# mach_nguyen_ly.net
KiCad netlist of a schematic drawn in Altium Designer
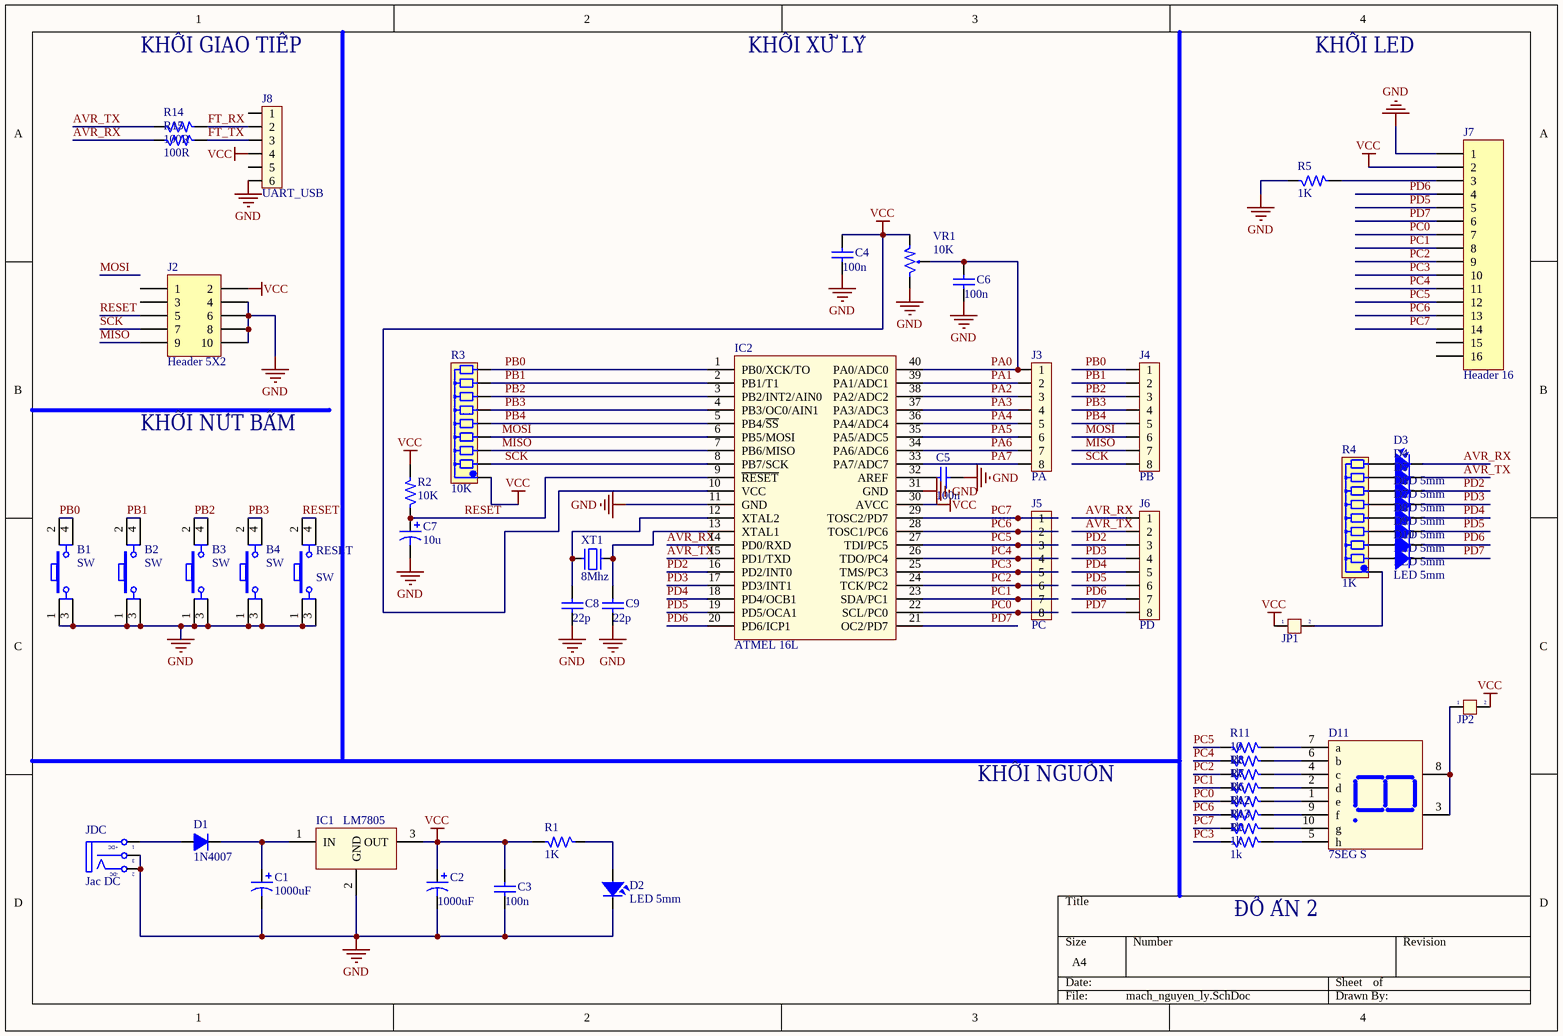
[diagram p0: mach_nguyen_ly.SchDoc]

(export (version "E")
  (design (tool "Eeschema 10.0.6"))
  (components
    (comp (ref "10")
      (value "1k")
      (footprint "R1/6W")
      (description "Resistor 1/4W")
      (libsource (lib "Cty1") (part "Res"))
    )
    (comp (ref "B1")
      (value "SW")
      (footprint "SW4")
      (description "Switch button 4 pin")
      (libsource (lib "Cty1") (part "SW4"))
    )
    (comp (ref "B2")
      (value "SW")
      (footprint "SW4")
      (description "Switch button 4 pin")
      (libsource (lib "Cty1") (part "SW4"))
    )
    (comp (ref "B3")
      (value "SW")
      (footprint "SW4")
      (description "Switch button 4 pin")
      (libsource (lib "Cty1") (part "SW4"))
    )
    (comp (ref "B4")
      (value "SW")
      (footprint "SW4")
      (description "Switch button 4 pin")
      (libsource (lib "Cty1") (part "SW4"))
    )
    (comp (ref "C1")
      (value "1000uF")
      (footprint "C10mm")
      (description "Polarized Capacitor (Axial)")
      (fields (field (name "PUBLISHER") "Altium Limited"))
      (libsource (lib "Cty1") (part "Cap Pol 12mm"))
    )
    (comp (ref "C2")
      (value "1000uF")
      (footprint "C10mm")
      (description "Polarized Capacitor (Axial)")
      (fields (field (name "PUBLISHER") "Altium Limited"))
      (libsource (lib "Cty1") (part "Cap Pol 12mm"))
    )
    (comp (ref "C3")
      (value "100n")
      (footprint "Tu-ceramic")
      (description "Capacitor")
      (fields (field (name "Comment") "Capacitor Ceramic") (field (name "PUBLISHER") "Altium Limited"))
      (libsource (lib "Cty1") (part "CapDecop"))
    )
    (comp (ref "C4")
      (value "100n")
      (footprint "Tu-ceramic")
      (description "Capacitor")
      (fields (field (name "Comment") "Capacitor Ceramic") (field (name "PUBLISHER") "Altium Limited"))
      (libsource (lib "Cty1") (part "CapDecop"))
    )
    (comp (ref "C5")
      (value "100n")
      (footprint "Tu-ceramic")
      (description "Capacitor")
      (fields (field (name "Comment") "Capacitor Ceramic") (field (name "PUBLISHER") "Altium Limited"))
      (libsource (lib "Cty1") (part "CapDecop"))
    )
    (comp (ref "C6")
      (value "100n")
      (footprint "Tu-ceramic")
      (description "Capacitor")
      (fields (field (name "Comment") "Capacitor Ceramic") (field (name "PUBLISHER") "Altium Limited"))
      (libsource (lib "Cty1") (part "CapDecop"))
    )
    (comp (ref "C7")
      (value "10u")
      (footprint "C5mm")
      (description "Polarized Capacitor (Axial)")
      (fields (field (name "PUBLISHER") "Altium Limited"))
      (libsource (lib "Cty1") (part "Cap Pol 5mm"))
    )
    (comp (ref "C8")
      (value "22p")
      (footprint "Tu-ceramic")
      (description "Capacitor")
      (fields (field (name "Comment") "Capacitor Ceramic") (field (name "PUBLISHER") "Altium Limited"))
      (libsource (lib "Cty1") (part "CapDecop"))
    )
    (comp (ref "C9")
      (value "22p")
      (footprint "Tu-ceramic")
      (description "Capacitor")
      (fields (field (name "Comment") "Capacitor Ceramic") (field (name "PUBLISHER") "Altium Limited"))
      (libsource (lib "Cty1") (part "CapDecop"))
    )
    (comp (ref "D1")
      (value "1N4007")
      (footprint "D1A")
      (description "Diode 1A")
      (libsource (lib "Cty1") (part "D1A"))
    )
    (comp (ref "D2")
      (value "LED 5mm")
      (footprint "LED-3")
      (description "LED Single colour Green and Red")
      (libsource (lib "VioletofSun") (part "LED"))
    )
    (comp (ref "D3")
      (value "LED 5mm")
      (footprint "LED-3")
      (description "LED Single colour Green and Red")
      (libsource (lib "VioletofSun") (part "LED"))
    )
    (comp (ref "D4")
      (value "LED 5mm")
      (footprint "LED-3")
      (description "LED Single colour Green and Red")
      (libsource (lib "VioletofSun") (part "LED"))
    )
    (comp (ref "D5")
      (value "LED 5mm")
      (footprint "LED-3")
      (description "LED Single colour Green and Red")
      (libsource (lib "VioletofSun") (part "LED"))
    )
    (comp (ref "D6")
      (value "LED 5mm")
      (footprint "LED-3")
      (description "LED Single colour Green and Red")
      (libsource (lib "VioletofSun") (part "LED"))
    )
    (comp (ref "D7")
      (value "LED 5mm")
      (footprint "LED-3")
      (description "LED Single colour Green and Red")
      (libsource (lib "VioletofSun") (part "LED"))
    )
    (comp (ref "D8")
      (value "LED 5mm")
      (footprint "LED-3")
      (description "LED Single colour Green and Red")
      (libsource (lib "VioletofSun") (part "LED"))
    )
    (comp (ref "D9")
      (value "LED 5mm")
      (footprint "LED-3")
      (description "LED Single colour Green and Red")
      (libsource (lib "VioletofSun") (part "LED"))
    )
    (comp (ref "D10")
      (value "LED 5mm")
      (footprint "LED-3")
      (description "LED Single colour Green and Red")
      (libsource (lib "VioletofSun") (part "LED"))
    )
    (comp (ref "D11")
      (value "7SEG S")
      (footprint "7SEGS")
      (description "Single 7 Seg Dipslay")
      (libsource (lib "Cty1") (part "LED7S"))
    )
    (comp (ref "IC1")
      (value "LM7805")
      (footprint "QTO-220")
      (description "On ap +, from + 5 to + 24VDC")
      (libsource (lib "Cty1") (part "LM78xx"))
    )
    (comp (ref "IC2")
      (value "ATMEL 16L")
      (footprint "DIP40/W0.6")
      (description "8-Bit AVR Microcontroller with 16K Bytes of In-System Programmable Flash Memory")
      (libsource (lib "Cty1") (part "Atmega16L"))
    )
    (comp (ref "J2")
      (value "Header 5X2")
      (footprint "HDR2X5")
      (description "Header, 5-Pin, Dual row")
      (fields (field (name "PUBLISHER") "Altium Limited"))
      (libsource (lib "Schematic") (part "Header 5X2"))
    )
    (comp (ref "J3")
      (value "PA")
      (footprint "JP8")
      (description "JP8 PIN")
      (libsource (lib "Cty1") (part "JP8"))
    )
    (comp (ref "J4")
      (value "PB")
      (footprint "JP8")
      (description "JP8 PIN")
      (libsource (lib "Cty1") (part "JP8"))
    )
    (comp (ref "J5")
      (value "PC")
      (footprint "JP8")
      (description "JP8 PIN")
      (libsource (lib "Cty1") (part "JP8"))
    )
    (comp (ref "J6")
      (value "PD")
      (footprint "JP8")
      (description "JP8 PIN")
      (libsource (lib "Cty1") (part "JP8"))
    )
    (comp (ref "J7")
      (value "Header 16")
      (footprint "HDR1X16")
      (description "Header, 16-Pin")
      (fields (field (name "PUBLISHER") "Altium Limited"))
      (libsource (lib "Cty1") (part "Header 16"))
    )
    (comp (ref "J8")
      (value "UART_USB")
      (footprint "JP6")
      (description "JP6 PIN")
      (libsource (lib "Cty1") (part "JP6_1"))
    )
    (comp (ref "JDC")
      (value "Jac DC")
      (footprint "DC-IN")
      (description "Jac DC input")
      (libsource (lib "Cty1") (part "DCIN"))
    )
    (comp (ref "JP1") (value "Jumper 2") (footprint "JP2") (libsource (lib "syhaunguyen") (part "JP 2")))
    (comp (ref "JP2") (value "Jumper 2") (footprint "JP2") (libsource (lib "syhaunguyen") (part "JP 2")))
    (comp (ref "R1")
      (value "1K")
      (footprint "R1/6W")
      (description "Resistor 1/4W")
      (libsource (lib "Cty1") (part "Res"))
    )
    (comp (ref "R2")
      (value "10K")
      (footprint "R1/6W")
      (description "Resistor 1/4W")
      (libsource (lib "Cty1") (part "Res"))
    )
    (comp (ref "R3")
      (value "10K")
      (footprint "RN8")
      (description "Resistor 8 (Thanh)")
      (libsource (lib "Cty1") (part "ResN8"))
    )
    (comp (ref "R4")
      (value "1K")
      (footprint "RN8")
      (description "Resistor 8 (Thanh)")
      (libsource (lib "Cty1") (part "ResN8"))
    )
    (comp (ref "R5")
      (value "1K")
      (footprint "R1/6W")
      (description "Resistor 1/4W")
      (libsource (lib "Cty1") (part "Res"))
    )
    (comp (ref "R6")
      (value "1k")
      (footprint "R1/6W")
      (description "Resistor 1/4W")
      (libsource (lib "Cty1") (part "Res"))
    )
    (comp (ref "R7")
      (value "1k")
      (footprint "R1/6W")
      (description "Resistor 1/4W")
      (libsource (lib "Cty1") (part "Res"))
    )
    (comp (ref "R8")
      (value "1k")
      (footprint "R1/6W")
      (description "Resistor 1/4W")
      (libsource (lib "Cty1") (part "Res"))
    )
    (comp (ref "R9")
      (value "1k")
      (footprint "R1/6W")
      (description "Resistor 1/4W")
      (libsource (lib "Cty1") (part "Res"))
    )
    (comp (ref "R11")
      (value "1k")
      (footprint "R1/6W")
      (description "Resistor 1/4W")
      (libsource (lib "Cty1") (part "Res"))
    )
    (comp (ref "R12")
      (value "1k")
      (footprint "R1/6W")
      (description "Resistor 1/4W")
      (libsource (lib "Cty1") (part "Res"))
    )
    (comp (ref "R13")
      (value "1k")
      (footprint "R1/6W")
      (description "Resistor 1/4W")
      (libsource (lib "Cty1") (part "Res"))
    )
    (comp (ref "R14")
      (value "100R")
      (footprint "R1/6W")
      (description "Resistor 1/4W")
      (libsource (lib "Cty1") (part "Res"))
    )
    (comp (ref "R15")
      (value "100R")
      (footprint "R1/6W")
      (description "Resistor 1/4W")
      (libsource (lib "Cty1") (part "Res"))
    )
    (comp (ref "RESET")
      (value "SW")
      (footprint "SW4")
      (description "Switch button 4 pin")
      (libsource (lib "Cty1") (part "SW4"))
    )
    (comp (ref "VR1")
      (value "10K")
      (footprint "VioletofSun:VR")
      (description "Var Resistor")
      (libsource (lib "VioletofSun") (part "VR1"))
    )
    (comp (ref "XT1")
      (value "8Mhz")
      (footprint "XT2")
      (description "Crystal For all Crystal 2pin.")
      (libsource (lib "syhaunguyen") (part "XT2"))
    )
  )
  (nets
    (net (code "1") (name "/AVR_RX") (class "Default")
      (node (ref "D3") (pin "2") (pinfunction "2_2") (pintype "passive"))
      (node (ref "IC2") (pin "14") (pinfunction "PD0/RXD_14") (pintype "passive"))
      (node (ref "J6") (pin "1") (pinfunction "1_1") (pintype "passive"))
      (node (ref "R15") (pin "1") (pinfunction "1_1") (pintype "passive"))
    )
    (net (code "2") (name "/AVR_TX") (class "Default")
      (node (ref "D4") (pin "2") (pinfunction "2_2") (pintype "passive"))
      (node (ref "IC2") (pin "15") (pinfunction "PD1/TXD_15") (pintype "passive"))
      (node (ref "J6") (pin "2") (pinfunction "2_2") (pintype "passive"))
      (node (ref "R14") (pin "1") (pinfunction "1_1") (pintype "passive"))
    )
    (net (code "3") (name "/FT_RX") (class "Default")
      (node (ref "J8") (pin "2") (pinfunction "2_2") (pintype "passive"))
      (node (ref "R14") (pin "2") (pinfunction "2_2") (pintype "passive"))
    )
    (net (code "4") (name "/FT_TX") (class "Default")
      (node (ref "J8") (pin "3") (pinfunction "3_3") (pintype "passive"))
      (node (ref "R15") (pin "2") (pinfunction "2_2") (pintype "passive"))
    )
    (net (code "5") (name "/MISO") (class "Default")
      (node (ref "IC2") (pin "7") (pinfunction "PB6/MISO_7") (pintype "passive"))
      (node (ref "J2") (pin "9") (pinfunction "9_9") (pintype "passive"))
      (node (ref "J4") (pin "7") (pinfunction "7_7") (pintype "passive"))
      (node (ref "R3") (pin "3") (pinfunction "3_3") (pintype "passive"))
    )
    (net (code "6") (name "/MOSI") (class "Default")
      (node (ref "IC2") (pin "6") (pinfunction "PB5/MOSI_6") (pintype "passive"))
      (node (ref "J4") (pin "6") (pinfunction "6_6") (pintype "passive"))
      (node (ref "R3") (pin "4") (pinfunction "4_4") (pintype "passive"))
    )
    (net (code "7") (name "/PA0") (class "Default")
      (node (ref "C6") (pin "2") (pinfunction "2_2") (pintype "passive"))
      (node (ref "IC2") (pin "40") (pinfunction "PA0/ADC0_40") (pintype "passive"))
      (node (ref "J3") (pin "1") (pinfunction "1_1") (pintype "passive"))
      (node (ref "VR1") (pin "2") (pinfunction "2_2") (pintype "passive"))
    )
    (net (code "8") (name "/PA1") (class "Default")
      (node (ref "IC2") (pin "39") (pinfunction "PA1/ADC1_39") (pintype "passive"))
      (node (ref "J3") (pin "2") (pinfunction "2_2") (pintype "passive"))
    )
    (net (code "9") (name "/PA2") (class "Default")
      (node (ref "IC2") (pin "38") (pinfunction "PA2/ADC2_38") (pintype "passive"))
      (node (ref "J3") (pin "3") (pinfunction "3_3") (pintype "passive"))
    )
    (net (code "10") (name "/PA3") (class "Default")
      (node (ref "IC2") (pin "37") (pinfunction "PA3/ADC3_37") (pintype "passive"))
      (node (ref "J3") (pin "4") (pinfunction "4_4") (pintype "passive"))
    )
    (net (code "11") (name "/PA4") (class "Default")
      (node (ref "IC2") (pin "36") (pinfunction "PA4/ADC4_36") (pintype "passive"))
      (node (ref "J3") (pin "5") (pinfunction "5_5") (pintype "passive"))
    )
    (net (code "12") (name "/PA5") (class "Default")
      (node (ref "IC2") (pin "35") (pinfunction "PA5/ADC5_35") (pintype "passive"))
      (node (ref "J3") (pin "6") (pinfunction "6_6") (pintype "passive"))
    )
    (net (code "13") (name "/PA6") (class "Default")
      (node (ref "IC2") (pin "34") (pinfunction "PA6/ADC6_34") (pintype "passive"))
      (node (ref "J3") (pin "7") (pinfunction "7_7") (pintype "passive"))
    )
    (net (code "14") (name "/PA7") (class "Default")
      (node (ref "IC2") (pin "33") (pinfunction "PA7/ADC7_33") (pintype "passive"))
      (node (ref "J3") (pin "8") (pinfunction "8_8") (pintype "passive"))
    )
    (net (code "15") (name "/PB0") (class "Default")
      (node (ref "B1") (pin "2") (pintype "passive"))
      (node (ref "B1") (pin "4") (pintype "passive"))
      (node (ref "IC2") (pin "1") (pinfunction "PB0/XCK/TO_1") (pintype "passive"))
      (node (ref "J4") (pin "1") (pinfunction "1_1") (pintype "passive"))
      (node (ref "R3") (pin "9") (pinfunction "9_9") (pintype "passive"))
    )
    (net (code "16") (name "/PB1") (class "Default")
      (node (ref "B2") (pin "2") (pintype "passive"))
      (node (ref "B2") (pin "4") (pintype "passive"))
      (node (ref "IC2") (pin "2") (pinfunction "PB1/T1_2") (pintype "passive"))
      (node (ref "J4") (pin "2") (pinfunction "2_2") (pintype "passive"))
      (node (ref "R3") (pin "8") (pinfunction "8_8") (pintype "passive"))
    )
    (net (code "17") (name "/PB2") (class "Default")
      (node (ref "B3") (pin "2") (pintype "passive"))
      (node (ref "B3") (pin "4") (pintype "passive"))
      (node (ref "IC2") (pin "3") (pinfunction "PB2/INT2/AIN0_3") (pintype "passive"))
      (node (ref "J4") (pin "3") (pinfunction "3_3") (pintype "passive"))
      (node (ref "R3") (pin "7") (pinfunction "7_7") (pintype "passive"))
    )
    (net (code "18") (name "/PB3") (class "Default")
      (node (ref "B4") (pin "2") (pintype "passive"))
      (node (ref "B4") (pin "4") (pintype "passive"))
      (node (ref "IC2") (pin "4") (pinfunction "PB3/OC0/AIN1_4") (pintype "passive"))
      (node (ref "J4") (pin "4") (pinfunction "4_4") (pintype "passive"))
      (node (ref "R3") (pin "6") (pinfunction "6_6") (pintype "passive"))
    )
    (net (code "19") (name "/PB4") (class "Default")
      (node (ref "IC2") (pin "5") (pinfunction "PB4/~{SS}_5") (pintype "passive"))
      (node (ref "J4") (pin "5") (pinfunction "5_5") (pintype "passive"))
      (node (ref "R3") (pin "5") (pinfunction "5_5") (pintype "passive"))
    )
    (net (code "20") (name "/PC0") (class "Default")
      (node (ref "IC2") (pin "22") (pinfunction "SCL/PC0_22") (pintype "passive"))
      (node (ref "J5") (pin "8") (pinfunction "8_8") (pintype "passive"))
      (node (ref "J7") (pin "7") (pinfunction "7_7") (pintype "passive"))
      (node (ref "R6") (pin "1") (pinfunction "1_1") (pintype "passive"))
    )
    (net (code "21") (name "/PC1") (class "Default")
      (node (ref "IC2") (pin "23") (pinfunction "SDA/PC1_23") (pintype "passive"))
      (node (ref "J5") (pin "7") (pinfunction "7_7") (pintype "passive"))
      (node (ref "J7") (pin "8") (pinfunction "8_8") (pintype "passive"))
      (node (ref "R7") (pin "1") (pinfunction "1_1") (pintype "passive"))
    )
    (net (code "22") (name "/PC2") (class "Default")
      (node (ref "IC2") (pin "24") (pinfunction "TCK/PC2_24") (pintype "passive"))
      (node (ref "J5") (pin "6") (pinfunction "6_6") (pintype "passive"))
      (node (ref "J7") (pin "9") (pinfunction "9_9") (pintype "passive"))
      (node (ref "R8") (pin "1") (pinfunction "1_1") (pintype "passive"))
    )
    (net (code "23") (name "/PC3") (class "Default")
      (node (ref "IC2") (pin "25") (pinfunction "TMS/PC3_25") (pintype "passive"))
      (node (ref "J5") (pin "5") (pinfunction "5_5") (pintype "passive"))
      (node (ref "J7") (pin "10") (pinfunction "10_10") (pintype "passive"))
      (node (ref "R9") (pin "1") (pinfunction "1_1") (pintype "passive"))
    )
    (net (code "24") (name "/PC4") (class "Default")
      (node (ref "10") (pin "1") (pinfunction "1_1") (pintype "passive"))
      (node (ref "IC2") (pin "26") (pinfunction "TDO/PC4_26") (pintype "passive"))
      (node (ref "J5") (pin "4") (pinfunction "4_4") (pintype "passive"))
      (node (ref "J7") (pin "11") (pinfunction "11_11") (pintype "passive"))
    )
    (net (code "25") (name "/PC5") (class "Default")
      (node (ref "IC2") (pin "27") (pinfunction "TDI/PC5_27") (pintype "passive"))
      (node (ref "J5") (pin "3") (pinfunction "3_3") (pintype "passive"))
      (node (ref "J7") (pin "12") (pinfunction "12_12") (pintype "passive"))
      (node (ref "R11") (pin "1") (pinfunction "1_1") (pintype "passive"))
    )
    (net (code "26") (name "/PC6") (class "Default")
      (node (ref "IC2") (pin "28") (pinfunction "TOSC1/PC6_28") (pintype "passive"))
      (node (ref "J5") (pin "2") (pinfunction "2_2") (pintype "passive"))
      (node (ref "J7") (pin "13") (pinfunction "13_13") (pintype "passive"))
      (node (ref "R12") (pin "1") (pinfunction "1_1") (pintype "passive"))
    )
    (net (code "27") (name "/PC7") (class "Default")
      (node (ref "IC2") (pin "29") (pinfunction "TOSC2/PD7_29") (pintype "passive"))
      (node (ref "J5") (pin "1") (pinfunction "1_1") (pintype "passive"))
      (node (ref "J7") (pin "14") (pinfunction "14_14") (pintype "passive"))
      (node (ref "R13") (pin "1") (pinfunction "1_1") (pintype "passive"))
    )
    (net (code "28") (name "/PD2") (class "Default")
      (node (ref "D5") (pin "2") (pinfunction "2_2") (pintype "passive"))
      (node (ref "IC2") (pin "16") (pinfunction "PD2/INT0_16") (pintype "passive"))
      (node (ref "J6") (pin "3") (pinfunction "3_3") (pintype "passive"))
    )
    (net (code "29") (name "/PD3") (class "Default")
      (node (ref "D6") (pin "2") (pinfunction "2_2") (pintype "passive"))
      (node (ref "IC2") (pin "17") (pinfunction "PD3/INT1_17") (pintype "passive"))
      (node (ref "J6") (pin "4") (pinfunction "4_4") (pintype "passive"))
    )
    (net (code "30") (name "/PD4") (class "Default")
      (node (ref "D7") (pin "2") (pinfunction "2_2") (pintype "passive"))
      (node (ref "IC2") (pin "18") (pinfunction "PD4/OCB1_18") (pintype "passive"))
      (node (ref "J6") (pin "5") (pinfunction "5_5") (pintype "passive"))
    )
    (net (code "31") (name "/PD5") (class "Default")
      (node (ref "D8") (pin "2") (pinfunction "2_2") (pintype "passive"))
      (node (ref "IC2") (pin "19") (pinfunction "PD5/OCA1_19") (pintype "passive"))
      (node (ref "J6") (pin "6") (pinfunction "6_6") (pintype "passive"))
      (node (ref "J7") (pin "5") (pinfunction "5_5") (pintype "passive"))
    )
    (net (code "32") (name "/PD6") (class "Default")
      (node (ref "D9") (pin "2") (pinfunction "2_2") (pintype "passive"))
      (node (ref "IC2") (pin "20") (pinfunction "PD6/ICP1_20") (pintype "passive"))
      (node (ref "J6") (pin "7") (pinfunction "7_7") (pintype "passive"))
      (node (ref "J7") (pin "4") (pinfunction "4_4") (pintype "passive"))
    )
    (net (code "33") (name "/PD7") (class "Default")
      (node (ref "D10") (pin "2") (pinfunction "2_2") (pintype "passive"))
      (node (ref "IC2") (pin "21") (pinfunction "OC2/PD7_21") (pintype "passive"))
      (node (ref "J6") (pin "8") (pinfunction "8_8") (pintype "passive"))
      (node (ref "J7") (pin "6") (pinfunction "6_6") (pintype "passive"))
    )
    (net (code "34") (name "/RESET") (class "Default")
      (node (ref "C7") (pin "1") (pinfunction "1_1") (pintype "passive"))
      (node (ref "IC2") (pin "9") (pinfunction "~{RESET}_9") (pintype "passive"))
      (node (ref "J2") (pin "5") (pinfunction "5_5") (pintype "passive"))
      (node (ref "R2") (pin "1") (pinfunction "1_1") (pintype "passive"))
      (node (ref "RESET") (pin "2") (pintype "passive"))
      (node (ref "RESET") (pin "4") (pintype "passive"))
    )
    (net (code "35") (name "/SCK") (class "Default")
      (node (ref "IC2") (pin "8") (pinfunction "PB7/SCK_8") (pintype "passive"))
      (node (ref "J2") (pin "7") (pinfunction "7_7") (pintype "passive"))
      (node (ref "J4") (pin "8") (pinfunction "8_8") (pintype "passive"))
      (node (ref "R3") (pin "2") (pinfunction "2_2") (pintype "passive"))
    )
    (net (code "36") (name "GND") (class "Default")
      (node (ref "B1") (pin "1") (pintype "passive"))
      (node (ref "B1") (pin "3") (pintype "passive"))
      (node (ref "B2") (pin "1") (pintype "passive"))
      (node (ref "B2") (pin "3") (pintype "passive"))
      (node (ref "B3") (pin "1") (pintype "passive"))
      (node (ref "B3") (pin "3") (pintype "passive"))
      (node (ref "B4") (pin "1") (pintype "passive"))
      (node (ref "B4") (pin "3") (pintype "passive"))
      (node (ref "C1") (pin "2") (pinfunction "2_2") (pintype "passive"))
      (node (ref "C2") (pin "2") (pinfunction "2_2") (pintype "passive"))
      (node (ref "C3") (pin "1") (pinfunction "1_1") (pintype "passive"))
      (node (ref "C4") (pin "1") (pinfunction "1_1") (pintype "passive"))
      (node (ref "C5") (pin "1") (pinfunction "1_1") (pintype "passive"))
      (node (ref "C6") (pin "1") (pinfunction "1_1") (pintype "passive"))
      (node (ref "C7") (pin "2") (pinfunction "2_2") (pintype "passive"))
      (node (ref "C8") (pin "1") (pinfunction "1_1") (pintype "passive"))
      (node (ref "C9") (pin "1") (pinfunction "1_1") (pintype "passive"))
      (node (ref "D2") (pin "2") (pinfunction "2_2") (pintype "passive"))
      (node (ref "IC1") (pin "2") (pinfunction "GND_2") (pintype "passive"))
      (node (ref "IC2") (pin "11") (pinfunction "GND_11") (pintype "passive"))
      (node (ref "IC2") (pin "31") (pinfunction "GND_31") (pintype "passive"))
      (node (ref "J2") (pin "10") (pinfunction "10_10") (pintype "passive"))
      (node (ref "J2") (pin "4") (pinfunction "4_4") (pintype "passive"))
      (node (ref "J2") (pin "6") (pinfunction "6_6") (pintype "passive"))
      (node (ref "J2") (pin "8") (pinfunction "8_8") (pintype "passive"))
      (node (ref "J7") (pin "1") (pinfunction "1_1") (pintype "passive"))
      (node (ref "J8") (pin "6") (pinfunction "6_6") (pintype "passive"))
      (node (ref "JDC") (pin "2") (pinfunction "TN_2") (pintype "passive"))
      (node (ref "JDC") (pin "3") (pinfunction "S_3") (pintype "power_in"))
      (node (ref "R5") (pin "1") (pinfunction "1_1") (pintype "passive"))
      (node (ref "RESET") (pin "1") (pintype "passive"))
      (node (ref "RESET") (pin "3") (pintype "passive"))
      (node (ref "VR1") (pin "3") (pinfunction "3_3") (pintype "passive"))
    )
    (net (code "37") (name "Net-(D1-A)") (class "Default")
      (node (ref "D1") (pin "1") (pinfunction "A_1") (pintype "passive"))
      (node (ref "JDC") (pin "1") (pinfunction "T_1") (pintype "passive"))
    )
    (net (code "38") (name "Net-(D1-K)") (class "Default")
      (node (ref "C1") (pin "1") (pinfunction "1_1") (pintype "passive"))
      (node (ref "D1") (pin "2") (pinfunction "K_2") (pintype "passive"))
      (node (ref "IC1") (pin "1") (pinfunction "IN_1") (pintype "passive"))
    )
    (net (code "39") (name "Net-(D2-Pad1)") (class "Default")
      (node (ref "D2") (pin "1") (pinfunction "1_1") (pintype "passive"))
      (node (ref "R1") (pin "1") (pinfunction "1_1") (pintype "passive"))
    )
    (net (code "40") (name "Net-(D3-Pad1)") (class "Default")
      (node (ref "D3") (pin "1") (pinfunction "1_1") (pintype "passive"))
      (node (ref "R4") (pin "9") (pinfunction "9_9") (pintype "passive"))
    )
    (net (code "41") (name "Net-(D4-Pad1)") (class "Default")
      (node (ref "D4") (pin "1") (pinfunction "1_1") (pintype "passive"))
      (node (ref "R4") (pin "8") (pinfunction "8_8") (pintype "passive"))
    )
    (net (code "42") (name "Net-(D5-Pad1)") (class "Default")
      (node (ref "D5") (pin "1") (pinfunction "1_1") (pintype "passive"))
      (node (ref "R4") (pin "7") (pinfunction "7_7") (pintype "passive"))
    )
    (net (code "43") (name "Net-(D6-Pad1)") (class "Default")
      (node (ref "D6") (pin "1") (pinfunction "1_1") (pintype "passive"))
      (node (ref "R4") (pin "6") (pinfunction "6_6") (pintype "passive"))
    )
    (net (code "44") (name "Net-(D7-Pad1)") (class "Default")
      (node (ref "D7") (pin "1") (pinfunction "1_1") (pintype "passive"))
      (node (ref "R4") (pin "5") (pinfunction "5_5") (pintype "passive"))
    )
    (net (code "45") (name "Net-(D8-Pad1)") (class "Default")
      (node (ref "D8") (pin "1") (pinfunction "1_1") (pintype "passive"))
      (node (ref "R4") (pin "4") (pinfunction "4_4") (pintype "passive"))
    )
    (net (code "46") (name "Net-(D9-Pad1)") (class "Default")
      (node (ref "D9") (pin "1") (pinfunction "1_1") (pintype "passive"))
      (node (ref "R4") (pin "3") (pinfunction "3_3") (pintype "passive"))
    )
    (net (code "47") (name "Net-(D10-Pad1)") (class "Default")
      (node (ref "D10") (pin "1") (pinfunction "1_1") (pintype "passive"))
      (node (ref "R4") (pin "2") (pinfunction "2_2") (pintype "passive"))
    )
    (net (code "48") (name "Net-(D11-Vcc-Pad3)") (class "Default")
      (node (ref "D11") (pin "3") (pinfunction "Vcc_3") (pintype "passive"))
      (node (ref "D11") (pin "8") (pinfunction "Vcc_8") (pintype "passive"))
      (node (ref "JP2") (pin "1") (pinfunction "1_1") (pintype "passive"))
    )
    (net (code "49") (name "Net-(D11-a)") (class "Default")
      (node (ref "D11") (pin "7") (pinfunction "a_7") (pintype "passive"))
      (node (ref "R11") (pin "2") (pinfunction "2_2") (pintype "passive"))
    )
    (net (code "50") (name "Net-(D11-b)") (class "Default")
      (node (ref "10") (pin "2") (pinfunction "2_2") (pintype "passive"))
      (node (ref "D11") (pin "6") (pinfunction "b_6") (pintype "passive"))
    )
    (net (code "51") (name "Net-(D11-c)") (class "Default")
      (node (ref "D11") (pin "4") (pinfunction "c_4") (pintype "passive"))
      (node (ref "R8") (pin "2") (pinfunction "2_2") (pintype "passive"))
    )
    (net (code "52") (name "Net-(D11-d)") (class "Default")
      (node (ref "D11") (pin "2") (pinfunction "d_2") (pintype "passive"))
      (node (ref "R7") (pin "2") (pinfunction "2_2") (pintype "passive"))
    )
    (net (code "53") (name "Net-(D11-e)") (class "Default")
      (node (ref "D11") (pin "1") (pinfunction "e_1") (pintype "passive"))
      (node (ref "R6") (pin "2") (pinfunction "2_2") (pintype "passive"))
    )
    (net (code "54") (name "Net-(D11-f)") (class "Default")
      (node (ref "D11") (pin "9") (pinfunction "f_9") (pintype "passive"))
      (node (ref "R12") (pin "2") (pinfunction "2_2") (pintype "passive"))
    )
    (net (code "55") (name "Net-(D11-g)") (class "Default")
      (node (ref "D11") (pin "10") (pinfunction "g_10") (pintype "passive"))
      (node (ref "R13") (pin "2") (pinfunction "2_2") (pintype "passive"))
    )
    (net (code "56") (name "Net-(D11-h)") (class "Default")
      (node (ref "D11") (pin "5") (pinfunction "h_5") (pintype "passive"))
      (node (ref "R9") (pin "2") (pinfunction "2_2") (pintype "passive"))
    )
    (net (code "57") (name "Net-(IC2-AREF)") (class "Default")
      (node (ref "C5") (pin "2") (pinfunction "2_2") (pintype "passive"))
      (node (ref "IC2") (pin "32") (pinfunction "AREF_32") (pintype "passive"))
    )
    (net (code "58") (name "Net-(IC2-XTAL1)") (class "Default")
      (node (ref "C9") (pin "2") (pinfunction "2_2") (pintype "passive"))
      (node (ref "IC2") (pin "13") (pinfunction "XTAL1_13") (pintype "passive"))
      (node (ref "XT1") (pin "2") (pinfunction "2_2") (pintype "passive"))
    )
    (net (code "59") (name "Net-(IC2-XTAL2)") (class "Default")
      (node (ref "C8") (pin "2") (pinfunction "2_2") (pintype "passive"))
      (node (ref "IC2") (pin "12") (pinfunction "XTAL2_12") (pintype "passive"))
      (node (ref "XT1") (pin "1") (pinfunction "1_1") (pintype "passive"))
    )
    (net (code "60") (name "Net-(J7-Pad3)") (class "Default")
      (node (ref "J7") (pin "3") (pinfunction "3_3") (pintype "passive"))
      (node (ref "R5") (pin "2") (pinfunction "2_2") (pintype "passive"))
    )
    (net (code "61") (name "Net-(JP1-Pad2)") (class "Default")
      (node (ref "JP1") (pin "2") (pinfunction "2_2") (pintype "passive"))
      (node (ref "R4") (pin "1") (pinfunction "1_1") (pintype "passive"))
    )
    (net (code "62") (name "VCC") (class "Default")
      (node (ref "C2") (pin "1") (pinfunction "1_1") (pintype "passive"))
      (node (ref "C3") (pin "2") (pinfunction "2_2") (pintype "passive"))
      (node (ref "C4") (pin "2") (pinfunction "2_2") (pintype "passive"))
      (node (ref "IC1") (pin "3") (pinfunction "OUT_3") (pintype "passive"))
      (node (ref "IC2") (pin "10") (pinfunction "VCC_10") (pintype "passive"))
      (node (ref "IC2") (pin "30") (pinfunction "AVCC_30") (pintype "passive"))
      (node (ref "J2") (pin "2") (pinfunction "2_2") (pintype "passive"))
      (node (ref "J7") (pin "2") (pinfunction "2_2") (pintype "passive"))
      (node (ref "J8") (pin "4") (pinfunction "4_4") (pintype "passive"))
      (node (ref "JP1") (pin "1") (pinfunction "1_1") (pintype "passive"))
      (node (ref "JP2") (pin "2") (pinfunction "2_2") (pintype "passive"))
      (node (ref "R1") (pin "2") (pinfunction "2_2") (pintype "passive"))
      (node (ref "R2") (pin "2") (pinfunction "2_2") (pintype "passive"))
      (node (ref "R3") (pin "1") (pinfunction "1_1") (pintype "passive"))
      (node (ref "VR1") (pin "1") (pinfunction "1_1") (pintype "passive"))
    )
    (net (code "63") (name "unconnected-(J2-Pad1)") (class "Default")
      (node (ref "J2") (pin "1") (pinfunction "1_1") (pintype "passive"))
    )
    (net (code "64") (name "unconnected-(J2-Pad3)") (class "Default")
      (node (ref "J2") (pin "3") (pinfunction "3_3") (pintype "passive"))
    )
    (net (code "65") (name "unconnected-(J7-Pad15)") (class "Default")
      (node (ref "J7") (pin "15") (pinfunction "15_15") (pintype "passive"))
    )
    (net (code "66") (name "unconnected-(J7-Pad16)") (class "Default")
      (node (ref "J7") (pin "16") (pinfunction "16_16") (pintype "passive"))
    )
    (net (code "67") (name "unconnected-(J8-Pad1)") (class "Default")
      (node (ref "J8") (pin "1") (pinfunction "1_1") (pintype "passive"))
    )
    (net (code "68") (name "unconnected-(J8-Pad5)") (class "Default")
      (node (ref "J8") (pin "5") (pinfunction "5_5") (pintype "passive"))
    )
  )
)
